# Option_Charger.net
KiCad netlist of a schematic drawn in Altium Designer
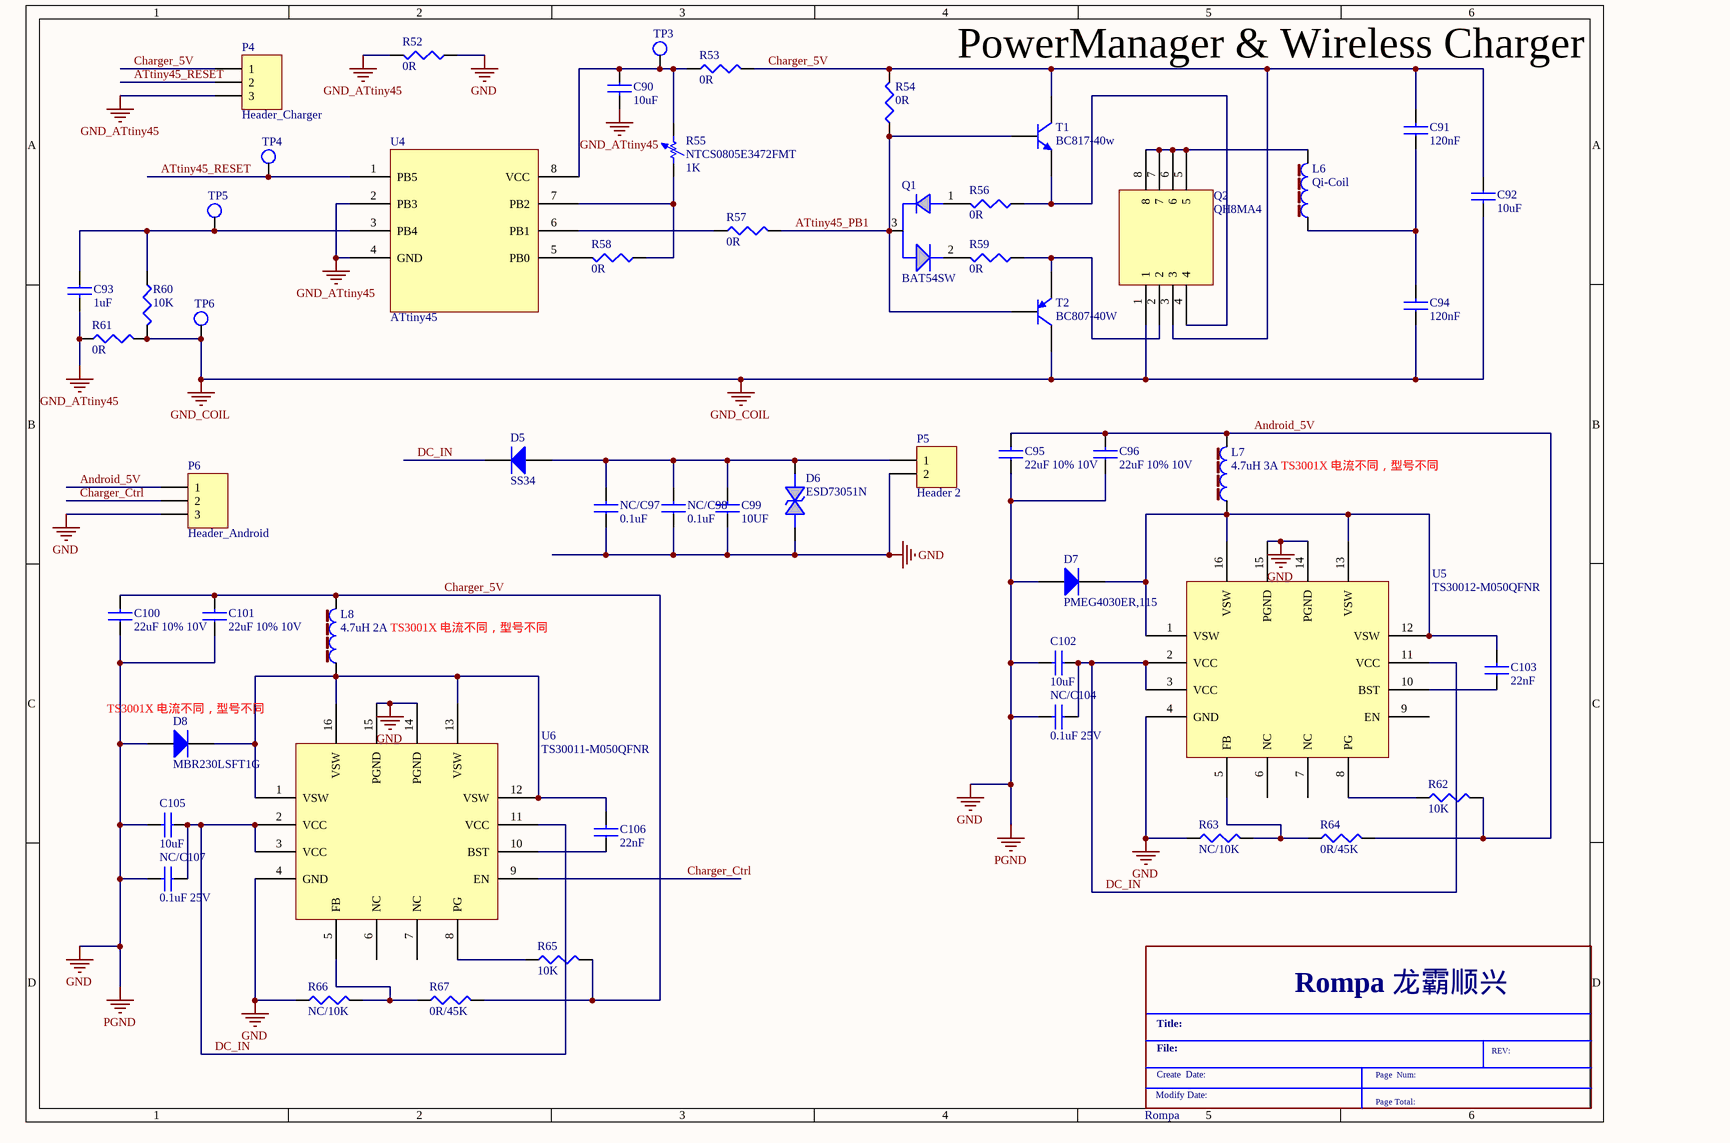
[diagram p0: Option_Charger.SchDoc]

(export (version "E")
  (design (tool "Eeschema 10.0.6"))
  (components
    (comp (ref "C90")
      (value "10uF")
      (footprint "2012[0805]")
      (description "C0805C106J8RACAUTO KEMET")
      (libsource (lib "RK3128_BETA_V03_20151231_Library") (part "CAP NP"))
    )
    (comp (ref "C91")
      (value "120nF")
      (footprint "C1206")
      (description "C1206C124J5RACTU KEMET  120nF, 50V, 5%, COG  CoiX7R (or better), 5%")
      (libsource (lib "RK3128_BETA_V03_20151231_Library") (part "CAP NP"))
    )
    (comp (ref "C92")
      (value "10uF")
      (footprint "C0805")
      (description "C0805C106J8RACAUTO KEMET 10U  CoiX7R (or better), 5%")
      (libsource (lib "RK3128_BETA_V03_20151231_Library") (part "CAP NP_Dup1"))
    )
    (comp (ref "C93")
      (value "1uF")
      (footprint "C0805")
      (description "C0805C105J3RACTU  KEMET")
      (libsource (lib "RK3128_BETA_V03_20151231_Library") (part "CAP NP"))
    )
    (comp (ref "C94")
      (value "120nF")
      (footprint "C1206")
      (description "C1206C124J5RACTU KEMET  120nF, 50V, 5%, COG  CoiX7R (or better), 5%")
      (libsource (lib "RK3128_BETA_V03_20151231_Library") (part "CAP NP"))
    )
    (comp (ref "C95")
      (value "22uF 10% 10V")
      (footprint "C0805")
      (description "C2012X5R1A226K125AB TDK")
      (libsource (lib "RK3128_BETA_V03_20151231_Library") (part "CAP NP"))
    )
    (comp (ref "C96")
      (value "22uF 10% 10V")
      (footprint "C0805")
      (description "C2012X5R1A226K125AB TDK")
      (libsource (lib "RK3128_BETA_V03_20151231_Library") (part "CAP NP"))
    )
    (comp (ref "C99")
      (value "10UF")
      (footprint "C1210")
      (description "CAP CER 10UF 50V X7S 1210  C3225X7S1H106M250AB  TDK Corporation")
      (libsource (lib "RK3128_BETA_V03_20151231_Library") (part "CAP NP"))
    )
    (comp (ref "C100")
      (value "22uF 10% 10V")
      (footprint "C0805")
      (description "C2012X5R1A226K125AB TDK")
      (libsource (lib "RK3128_BETA_V03_20151231_Library") (part "CAP NP"))
    )
    (comp (ref "C101")
      (value "22uF 10% 10V")
      (footprint "C0805")
      (description "C2012X5R1A226K125AB TDK")
      (libsource (lib "RK3128_BETA_V03_20151231_Library") (part "CAP NP"))
    )
    (comp (ref "C102")
      (value "10uF")
      (footprint "C1206")
      (description "Capacitor  10uF 10% 35V TDK CGA5L3X5R1V106K160AB")
      (libsource (lib "RK3128_BETA_V03_20151231_Library") (part "CAP NP"))
    )
    (comp (ref "C103")
      (value "22nF")
      (footprint "C0402")
      (description "15nF-200nF 10V TDK C1005X7R1C223K")
      (libsource (lib "RK3128_BETA_V03_20151231_Library") (part "CAP NP"))
    )
    (comp (ref "C105")
      (value "10uF")
      (footprint "C1206")
      (description "Capacitor  10uF 10% 35V TDK CGA5L3X5R1V106K160AB")
      (libsource (lib "RK3128_BETA_V03_20151231_Library") (part "CAP NP"))
    )
    (comp (ref "C106")
      (value "22nF")
      (footprint "C0402")
      (description "15nF-200nF 10V TDK C1005X7R1C223K")
      (libsource (lib "RK3128_BETA_V03_20151231_Library") (part "CAP NP"))
    )
    (comp (ref "D5")
      (value "SS34")
      (description "Fairchild/ON Semiconductor     DO-214AB, SMC")
      (fields (field (name "PUBLISHER") "Altium Limited"))
      (libsource (lib "Miscellaneous Devices") (part "Diode"))
    )
    (comp (ref "D6")
      (value "ESD73051N")
      (description "FP=DFN1006-2L")
      (libsource (lib "RK3128_BETA_V03_20151231_Library") (part "DIODE BI-DIR TRIG"))
    )
    (comp (ref "D7")
      (value "PMEG4030ER,115")
      (description "40V 3A  SOD-123 NXP Semiconductors")
      (fields (field (name "PUBLISHER") "Altium Limited"))
      (libsource (lib "Miscellaneous Devices") (part "Diode"))
    )
    (comp (ref "D8")
      (value "MBR230LSFT1G")
      (description "30V 2A  SOD-123FL On Semiconductor MBR230LSFT1G")
      (fields (field (name "PUBLISHER") "Altium Limited"))
      (libsource (lib "Miscellaneous Devices") (part "Diode"))
    )
    (comp (ref "L6")
      (value "Qi-Coil")
      (libsource (lib "RK3128_BETA_V03_20151231_Library") (part "INDUCTOR_2"))
    )
    (comp (ref "L7")
      (value "4.7uH 3A")
      (description "4.7uH 3A TDK-----VLC5045T-4R7M   /  Wurth-----744774047")
      (libsource (lib "RK3128_BETA_V03_20151231_Library") (part "INDUCTOR_2"))
    )
    (comp (ref "L8")
      (value "4.7uH 2A")
      (description "4.7uH 2A     TDK---SLF7045T-4R7M2R0-PF  Wurth-----7447745047")
      (libsource (lib "RK3128_BETA_V03_20151231_Library") (part "INDUCTOR_2"))
    )
    (comp (ref "NC/C97")
      (value "0.1uF")
      (footprint "C0805")
      (description "CGA3E2X7R1H104K080AA  TDK Corporation    0.1μF  ±10%  50V  X7R")
      (libsource (lib "RK3128_BETA_V03_20151231_Library") (part "CAP NP"))
    )
    (comp (ref "NC/C98")
      (value "0.1uF")
      (footprint "C0805")
      (description "CGA3E2X7R1H104K080AA  TDK Corporation    0.1μF  ±10%  50V  X7R")
      (libsource (lib "RK3128_BETA_V03_20151231_Library") (part "CAP NP"))
    )
    (comp (ref "NC/C104")
      (value "0.1uF 25V")
      (footprint "C0402")
      (libsource (lib "RK3128_BETA_V03_20151231_Library") (part "CAP NP"))
    )
    (comp (ref "NC/C107")
      (value "0.1uF 25V")
      (footprint "C0402")
      (libsource (lib "RK3128_BETA_V03_20151231_Library") (part "CAP NP"))
    )
    (comp (ref "P4")
      (value "Header_Charger")
      (footprint "HDR1X3")
      (description "Header, 3-Pin")
      (fields (field (name "PUBLISHER") "Altium Limited"))
      (libsource (lib "Miscellaneous Connectors") (part "Header 3"))
    )
    (comp (ref "P5")
      (value "Header 2")
      (footprint "HDR1X2")
      (description "Header, 2-Pin")
      (fields (field (name "PUBLISHER") "Altium Limited"))
      (libsource (lib "Miscellaneous Connectors") (part "Header 2"))
    )
    (comp (ref "P6")
      (value "Header_Android")
      (footprint "HDR1X3")
      (description "Header, 3-Pin")
      (fields (field (name "PUBLISHER") "Altium Limited"))
      (libsource (lib "Miscellaneous Connectors") (part "Header 3"))
    )
    (comp (ref "Q1")
      (value "BAT54SW")
      (description "SOT323")
      (libsource (lib "iguide_custom") (part "BAT54SW"))
    )
    (comp (ref "Q2")
      (value "QH8MA4")
      (footprint "TSMT8")
      (description "TSMT8")
      (libsource (lib "iguide_custom") (part "QH8MA4"))
    )
    (comp (ref "R52")
      (value "0R")
      (footprint "R0402")
      (libsource (lib "RK3128_BETA_V03_20151231_Library") (part "RESISTOR"))
    )
    (comp (ref "R53")
      (value "0R")
      (footprint "R0402")
      (libsource (lib "RK3128_BETA_V03_20151231_Library") (part "RESISTOR"))
    )
    (comp (ref "R54")
      (value "0R")
      (footprint "R0402")
      (libsource (lib "RK3128_BETA_V03_20151231_Library") (part "RESISTOR"))
    )
    (comp (ref "R55")
      (value "NTCS0805E3472FMT")
      (footprint "2012[0805]")
      (description "4K7 NTC 1%")
      (fields (field (name "ALTIUM_VALUE") "1K") (field (name "PUBLISHER") "Altium Limited"))
      (libsource (lib "Miscellaneous Devices") (part "Res Adj1"))
    )
    (comp (ref "R56")
      (value "0R")
      (footprint "R0402")
      (libsource (lib "RK3128_BETA_V03_20151231_Library") (part "RESISTOR"))
    )
    (comp (ref "R57")
      (value "0R")
      (footprint "R0402")
      (libsource (lib "RK3128_BETA_V03_20151231_Library") (part "RESISTOR"))
    )
    (comp (ref "R58")
      (value "0R")
      (footprint "R0402")
      (libsource (lib "RK3128_BETA_V03_20151231_Library") (part "RESISTOR"))
    )
    (comp (ref "R59")
      (value "0R")
      (footprint "R0402")
      (libsource (lib "RK3128_BETA_V03_20151231_Library") (part "RESISTOR"))
    )
    (comp (ref "R60")
      (value "10K")
      (footprint "1608[0603]")
      (description "RC0603FR-0710KL Yageo")
      (libsource (lib "RK3128_BETA_V03_20151231_Library") (part "RESISTOR"))
    )
    (comp (ref "R61")
      (value "0R")
      (footprint "R0402")
      (libsource (lib "RK3128_BETA_V03_20151231_Library") (part "RESISTOR"))
    )
    (comp (ref "R62")
      (value "10K")
      (footprint "R0402")
      (libsource (lib "RK3128_BETA_V03_20151231_Library") (part "RESISTOR"))
    )
    (comp (ref "R63")
      (value "NC/10K")
      (footprint "R0402")
      (libsource (lib "RK3128_BETA_V03_20151231_Library") (part "RESISTOR"))
    )
    (comp (ref "R64")
      (value "0R/45K")
      (footprint "R0402")
      (libsource (lib "RK3128_BETA_V03_20151231_Library") (part "RESISTOR"))
    )
    (comp (ref "R65")
      (value "10K")
      (footprint "R0402")
      (libsource (lib "RK3128_BETA_V03_20151231_Library") (part "RESISTOR"))
    )
    (comp (ref "R66")
      (value "NC/10K")
      (footprint "R0402")
      (libsource (lib "RK3128_BETA_V03_20151231_Library") (part "RESISTOR"))
    )
    (comp (ref "R67")
      (value "0R/45K")
      (footprint "R0402")
      (libsource (lib "RK3128_BETA_V03_20151231_Library") (part "RESISTOR"))
    )
    (comp (ref "T1")
      (value "BC817-40w")
      (description "SOT323")
      (fields (field (name "PUBLISHER") "Altium Limited"))
      (libsource (lib "Miscellaneous Devices") (part "2N3904"))
    )
    (comp (ref "T2")
      (value "BC807-40W")
      (description "SOT323")
      (fields (field (name "PUBLISHER") "Altium Limited"))
      (libsource (lib "Miscellaneous Devices") (part "2N3906"))
    )
    (comp (ref "TP3")
      (value "~")
      (footprint "TEST")
      (libsource (lib "RK3128_BETA_V03_20151231_Library") (part "TESTPOINT1_0"))
    )
    (comp (ref "TP4")
      (value "~")
      (footprint "TEST")
      (libsource (lib "RK3128_BETA_V03_20151231_Library") (part "TESTPOINT1_0"))
    )
    (comp (ref "TP5")
      (value "~")
      (footprint "TEST")
      (libsource (lib "RK3128_BETA_V03_20151231_Library") (part "TESTPOINT1_0"))
    )
    (comp (ref "TP6")
      (value "~")
      (footprint "TEST")
      (libsource (lib "RK3128_BETA_V03_20151231_Library") (part "TESTPOINT1_0"))
    )
    (comp (ref "U4")
      (value "ATtiny45")
      (footprint "8 pin SOIC_M")
      (libsource (lib "iguide_custom") (part "ATtiny45"))
    )
    (comp (ref "U5")
      (value "TS30012-M050QFNR")
      (footprint "16-QFN")
      (libsource (lib "*") (part "TS30012-M050QFNR"))
    )
    (comp (ref "U6")
      (value "TS30011-M050QFNR")
      (footprint "16-QFN")
      (libsource (lib "*") (part "TS30012-M050QFNR"))
    )
  )
  (nets
    (net (code "1") (name "/ATtiny45_PB1") (class "Default")
      (node (ref "Q1") (pin "3") (pinfunction "K_3") (pintype "passive"))
      (node (ref "R54") (pin "1") (pinfunction "1_1") (pintype "passive"))
      (node (ref "R57") (pin "2") (pinfunction "2_2") (pintype "passive"))
      (node (ref "T1") (pin "2") (pinfunction "B_2") (pintype "passive"))
      (node (ref "T2") (pin "2") (pinfunction "B_2") (pintype "passive"))
    )
    (net (code "2") (name "/ATtiny45_RESET") (class "Default")
      (node (ref "P4") (pin "2") (pinfunction "2_2") (pintype "passive"))
      (node (ref "TP4") (pin "1") (pinfunction "1_1") (pintype "passive"))
      (node (ref "U4") (pin "1") (pinfunction "PB5_1") (pintype "passive"))
    )
    (net (code "3") (name "/Android_5V") (class "Default")
      (node (ref "C95") (pin "2") (pinfunction "2_2") (pintype "passive"))
      (node (ref "C96") (pin "2") (pinfunction "2_2") (pintype "passive"))
      (node (ref "L7") (pin "2") (pinfunction "2_2") (pintype "passive"))
      (node (ref "P6") (pin "1") (pinfunction "1_1") (pintype "passive"))
      (node (ref "R62") (pin "2") (pinfunction "2_2") (pintype "passive"))
      (node (ref "R64") (pin "2") (pinfunction "2_2") (pintype "passive"))
    )
    (net (code "4") (name "/Charger_5V") (class "Default")
      (node (ref "C100") (pin "2") (pinfunction "2_2") (pintype "passive"))
      (node (ref "C101") (pin "2") (pinfunction "2_2") (pintype "passive"))
      (node (ref "C91") (pin "2") (pinfunction "2_2") (pintype "passive"))
      (node (ref "C92") (pin "1") (pinfunction "1_1") (pintype "passive"))
      (node (ref "L8") (pin "2") (pinfunction "2_2") (pintype "passive"))
      (node (ref "P4") (pin "1") (pinfunction "1_1") (pintype "passive"))
      (node (ref "Q2") (pin "3") (pinfunction "3_3") (pintype "passive"))
      (node (ref "R53") (pin "2") (pinfunction "2_2") (pintype "passive"))
      (node (ref "R54") (pin "2") (pinfunction "2_2") (pintype "passive"))
      (node (ref "R65") (pin "2") (pinfunction "2_2") (pintype "passive"))
      (node (ref "R67") (pin "2") (pinfunction "2_2") (pintype "passive"))
      (node (ref "T1") (pin "3") (pinfunction "C_3") (pintype "passive"))
    )
    (net (code "5") (name "/Charger_Ctrl") (class "Default")
      (node (ref "P6") (pin "2") (pinfunction "2_2") (pintype "passive"))
      (node (ref "U6") (pin "9") (pinfunction "EN_9") (pintype "passive"))
    )
    (net (code "6") (name "/DC_IN") (class "Default")
      (node (ref "C102") (pin "1") (pinfunction "1_1") (pintype "passive"))
      (node (ref "C105") (pin "1") (pinfunction "1_1") (pintype "passive"))
      (node (ref "D5") (pin "2") (pinfunction "K_2") (pintype "passive"))
      (node (ref "NC/C104") (pin "1") (pinfunction "1_1") (pintype "passive"))
      (node (ref "NC/C107") (pin "1") (pinfunction "1_1") (pintype "passive"))
      (node (ref "U5") (pin "11") (pinfunction "VCC_11") (pintype "passive"))
      (node (ref "U5") (pin "2") (pinfunction "VCC_2") (pintype "passive"))
      (node (ref "U5") (pin "3") (pinfunction "VCC_3") (pintype "passive"))
      (node (ref "U6") (pin "11") (pinfunction "VCC_11") (pintype "passive"))
      (node (ref "U6") (pin "2") (pinfunction "VCC_2") (pintype "passive"))
      (node (ref "U6") (pin "3") (pinfunction "VCC_3") (pintype "passive"))
    )
    (net (code "7") (name "GND") (class "Default")
      (node (ref "C100") (pin "1") (pinfunction "1_1") (pintype "passive"))
      (node (ref "C101") (pin "1") (pinfunction "1_1") (pintype "passive"))
      (node (ref "C102") (pin "2") (pinfunction "2_2") (pintype "passive"))
      (node (ref "C105") (pin "2") (pinfunction "2_2") (pintype "passive"))
      (node (ref "C95") (pin "1") (pinfunction "1_1") (pintype "passive"))
      (node (ref "C96") (pin "1") (pinfunction "1_1") (pintype "passive"))
      (node (ref "C99") (pin "1") (pinfunction "1_1") (pintype "passive"))
      (node (ref "D6") (pin "1") (pinfunction "1_1") (pintype "passive"))
      (node (ref "D7") (pin "1") (pinfunction "A_1") (pintype "passive"))
      (node (ref "D8") (pin "1") (pinfunction "A_1") (pintype "passive"))
      (node (ref "NC/C104") (pin "2") (pinfunction "2_2") (pintype "passive"))
      (node (ref "NC/C107") (pin "2") (pinfunction "2_2") (pintype "passive"))
      (node (ref "NC/C97") (pin "1") (pinfunction "1_1") (pintype "passive"))
      (node (ref "NC/C98") (pin "1") (pinfunction "1_1") (pintype "passive"))
      (node (ref "P5") (pin "2") (pinfunction "2_2") (pintype "passive"))
      (node (ref "P6") (pin "3") (pinfunction "3_3") (pintype "passive"))
      (node (ref "R52") (pin "1") (pinfunction "1_1") (pintype "passive"))
      (node (ref "R63") (pin "1") (pinfunction "1_1") (pintype "passive"))
      (node (ref "R66") (pin "1") (pinfunction "1_1") (pintype "passive"))
      (node (ref "U5") (pin "14") (pinfunction "PGND_14") (pintype "passive"))
      (node (ref "U5") (pin "15") (pinfunction "PGND_15") (pintype "passive"))
      (node (ref "U5") (pin "4") (pinfunction "GND_4") (pintype "passive"))
      (node (ref "U6") (pin "14") (pinfunction "PGND_14") (pintype "passive"))
      (node (ref "U6") (pin "15") (pinfunction "PGND_15") (pintype "passive"))
      (node (ref "U6") (pin "4") (pinfunction "GND_4") (pintype "passive"))
    )
    (net (code "8") (name "GND_ATtiny45") (class "Default")
      (node (ref "C90") (pin "2") (pinfunction "2_2") (pintype "passive"))
      (node (ref "C93") (pin "2") (pinfunction "2_2") (pintype "passive"))
      (node (ref "P4") (pin "3") (pinfunction "3_3") (pintype "passive"))
      (node (ref "R52") (pin "2") (pinfunction "2_2") (pintype "passive"))
      (node (ref "R61") (pin "1") (pinfunction "1_1") (pintype "passive"))
      (node (ref "U4") (pin "2") (pinfunction "PB3_2") (pintype "passive"))
      (node (ref "U4") (pin "4") (pinfunction "GND_4") (pintype "passive"))
    )
    (net (code "9") (name "GND_COIL") (class "Default")
      (node (ref "C92") (pin "2") (pinfunction "2_2") (pintype "passive"))
      (node (ref "C94") (pin "1") (pinfunction "1_1") (pintype "passive"))
      (node (ref "Q2") (pin "1") (pinfunction "1_1") (pintype "passive"))
      (node (ref "R60") (pin "2") (pinfunction "2_2") (pintype "passive"))
      (node (ref "R61") (pin "2") (pinfunction "2_2") (pintype "passive"))
      (node (ref "T2") (pin "3") (pinfunction "C_3") (pintype "passive"))
      (node (ref "TP6") (pin "1") (pinfunction "1_1") (pintype "passive"))
    )
    (net (code "10") (name "Net-(C91-Pad1)") (class "Default")
      (node (ref "C91") (pin "1") (pinfunction "1_1") (pintype "passive"))
      (node (ref "C94") (pin "2") (pinfunction "2_2") (pintype "passive"))
      (node (ref "L6") (pin "1") (pinfunction "1_1") (pintype "passive"))
    )
    (net (code "11") (name "Net-(D5-A)") (class "Default")
      (node (ref "C99") (pin "2") (pinfunction "2_2") (pintype "passive"))
      (node (ref "D5") (pin "1") (pinfunction "A_1") (pintype "passive"))
      (node (ref "D6") (pin "2") (pinfunction "2_2") (pintype "passive"))
      (node (ref "NC/C97") (pin "2") (pinfunction "2_2") (pintype "passive"))
      (node (ref "NC/C98") (pin "2") (pinfunction "2_2") (pintype "passive"))
      (node (ref "P5") (pin "1") (pinfunction "1_1") (pintype "passive"))
    )
    (net (code "12") (name "Net-(D7-K)") (class "Default")
      (node (ref "C103") (pin "2") (pinfunction "2_2") (pintype "passive"))
      (node (ref "D7") (pin "2") (pinfunction "K_2") (pintype "passive"))
      (node (ref "L7") (pin "1") (pinfunction "1_1") (pintype "passive"))
      (node (ref "U5") (pin "1") (pinfunction "VSW_1") (pintype "passive"))
      (node (ref "U5") (pin "12") (pinfunction "VSW_12") (pintype "passive"))
      (node (ref "U5") (pin "13") (pinfunction "VSW_13") (pintype "passive"))
      (node (ref "U5") (pin "16") (pinfunction "VSW_16") (pintype "passive"))
    )
    (net (code "13") (name "Net-(D8-K)") (class "Default")
      (node (ref "C106") (pin "2") (pinfunction "2_2") (pintype "passive"))
      (node (ref "D8") (pin "2") (pinfunction "K_2") (pintype "passive"))
      (node (ref "L8") (pin "1") (pinfunction "1_1") (pintype "passive"))
      (node (ref "U6") (pin "1") (pinfunction "VSW_1") (pintype "passive"))
      (node (ref "U6") (pin "12") (pinfunction "VSW_12") (pintype "passive"))
      (node (ref "U6") (pin "13") (pinfunction "VSW_13") (pintype "passive"))
      (node (ref "U6") (pin "16") (pinfunction "VSW_16") (pintype "passive"))
    )
    (net (code "14") (name "Net-(L6-Pad2)") (class "Default")
      (node (ref "L6") (pin "2") (pinfunction "2_2") (pintype "passive"))
      (node (ref "Q2") (pin "5") (pinfunction "5_5") (pintype "passive"))
      (node (ref "Q2") (pin "6") (pinfunction "6_6") (pintype "passive"))
      (node (ref "Q2") (pin "7") (pinfunction "7_7") (pintype "passive"))
      (node (ref "Q2") (pin "8") (pinfunction "8_8") (pintype "passive"))
    )
    (net (code "15") (name "Net-(Q1-A1)") (class "Default")
      (node (ref "Q1") (pin "1") (pinfunction "A1_1") (pintype "passive"))
      (node (ref "R56") (pin "2") (pinfunction "2_2") (pintype "passive"))
    )
    (net (code "16") (name "Net-(Q1-A2)") (class "Default")
      (node (ref "Q1") (pin "2") (pinfunction "A2_2") (pintype "passive"))
      (node (ref "R59") (pin "2") (pinfunction "2_2") (pintype "passive"))
    )
    (net (code "17") (name "Net-(T1-E)") (class "Default")
      (node (ref "Q2") (pin "4") (pinfunction "4_4") (pintype "passive"))
      (node (ref "R56") (pin "1") (pinfunction "1_1") (pintype "passive"))
      (node (ref "T1") (pin "1") (pinfunction "E_1") (pintype "passive"))
    )
    (net (code "18") (name "Net-(T2-E)") (class "Default")
      (node (ref "Q2") (pin "2") (pinfunction "2_2") (pintype "passive"))
      (node (ref "R59") (pin "1") (pinfunction "1_1") (pintype "passive"))
      (node (ref "T2") (pin "1") (pinfunction "E_1") (pintype "passive"))
    )
    (net (code "19") (name "Net-(U4-PB0)") (class "Default")
      (node (ref "R58") (pin "2") (pinfunction "2_2") (pintype "passive"))
      (node (ref "U4") (pin "5") (pinfunction "PB0_5") (pintype "passive"))
    )
    (net (code "20") (name "Net-(U4-PB1)") (class "Default")
      (node (ref "R57") (pin "1") (pinfunction "1_1") (pintype "passive"))
      (node (ref "U4") (pin "6") (pinfunction "PB1_6") (pintype "passive"))
    )
    (net (code "21") (name "Net-(U4-PB2)") (class "Default")
      (node (ref "R55") (pin "1") (pinfunction "1_1") (pintype "passive"))
      (node (ref "R58") (pin "1") (pinfunction "1_1") (pintype "passive"))
      (node (ref "U4") (pin "7") (pinfunction "PB2_7") (pintype "passive"))
    )
    (net (code "22") (name "Net-(U4-PB4)") (class "Default")
      (node (ref "C93") (pin "1") (pinfunction "1_1") (pintype "passive"))
      (node (ref "R60") (pin "1") (pinfunction "1_1") (pintype "passive"))
      (node (ref "TP5") (pin "1") (pinfunction "1_1") (pintype "passive"))
      (node (ref "U4") (pin "3") (pinfunction "PB4_3") (pintype "passive"))
    )
    (net (code "23") (name "Net-(U4-VCC)") (class "Default")
      (node (ref "C90") (pin "1") (pinfunction "1_1") (pintype "passive"))
      (node (ref "R53") (pin "1") (pinfunction "1_1") (pintype "passive"))
      (node (ref "R55") (pin "2") (pinfunction "2_2") (pintype "passive"))
      (node (ref "TP3") (pin "1") (pinfunction "1_1") (pintype "passive"))
      (node (ref "U4") (pin "8") (pinfunction "VCC_8") (pintype "passive"))
    )
    (net (code "24") (name "Net-(U5-BST)") (class "Default")
      (node (ref "C103") (pin "1") (pinfunction "1_1") (pintype "passive"))
      (node (ref "U5") (pin "10") (pinfunction "BST_10") (pintype "passive"))
    )
    (net (code "25") (name "Net-(U5-FB)") (class "Default")
      (node (ref "R63") (pin "2") (pinfunction "2_2") (pintype "passive"))
      (node (ref "R64") (pin "1") (pinfunction "1_1") (pintype "passive"))
      (node (ref "U5") (pin "5") (pinfunction "FB_5") (pintype "passive"))
    )
    (net (code "26") (name "Net-(U5-PG)") (class "Default")
      (node (ref "R62") (pin "1") (pinfunction "1_1") (pintype "passive"))
      (node (ref "U5") (pin "8") (pinfunction "PG_8") (pintype "passive"))
    )
    (net (code "27") (name "Net-(U6-BST)") (class "Default")
      (node (ref "C106") (pin "1") (pinfunction "1_1") (pintype "passive"))
      (node (ref "U6") (pin "10") (pinfunction "BST_10") (pintype "passive"))
    )
    (net (code "28") (name "Net-(U6-FB)") (class "Default")
      (node (ref "R66") (pin "2") (pinfunction "2_2") (pintype "passive"))
      (node (ref "R67") (pin "1") (pinfunction "1_1") (pintype "passive"))
      (node (ref "U6") (pin "5") (pinfunction "FB_5") (pintype "passive"))
    )
    (net (code "29") (name "Net-(U6-PG)") (class "Default")
      (node (ref "R65") (pin "1") (pinfunction "1_1") (pintype "passive"))
      (node (ref "U6") (pin "8") (pinfunction "PG_8") (pintype "passive"))
    )
    (net (code "30") (name "unconnected-(U5-EN-Pad9)") (class "Default")
      (node (ref "U5") (pin "9") (pinfunction "EN_9") (pintype "passive"))
    )
    (net (code "31") (name "unconnected-(U5-NC-Pad6)") (class "Default")
      (node (ref "U5") (pin "6") (pinfunction "NC_6") (pintype "passive"))
    )
    (net (code "32") (name "unconnected-(U5-NC-Pad7)") (class "Default")
      (node (ref "U5") (pin "7") (pinfunction "NC_7") (pintype "passive"))
    )
    (net (code "33") (name "unconnected-(U6-NC-Pad6)") (class "Default")
      (node (ref "U6") (pin "6") (pinfunction "NC_6") (pintype "passive"))
    )
    (net (code "34") (name "unconnected-(U6-NC-Pad7)") (class "Default")
      (node (ref "U6") (pin "7") (pinfunction "NC_7") (pintype "passive"))
    )
  )
)
